# LedMatrix.net
KiCad netlist of a schematic drawn in Altium Designer
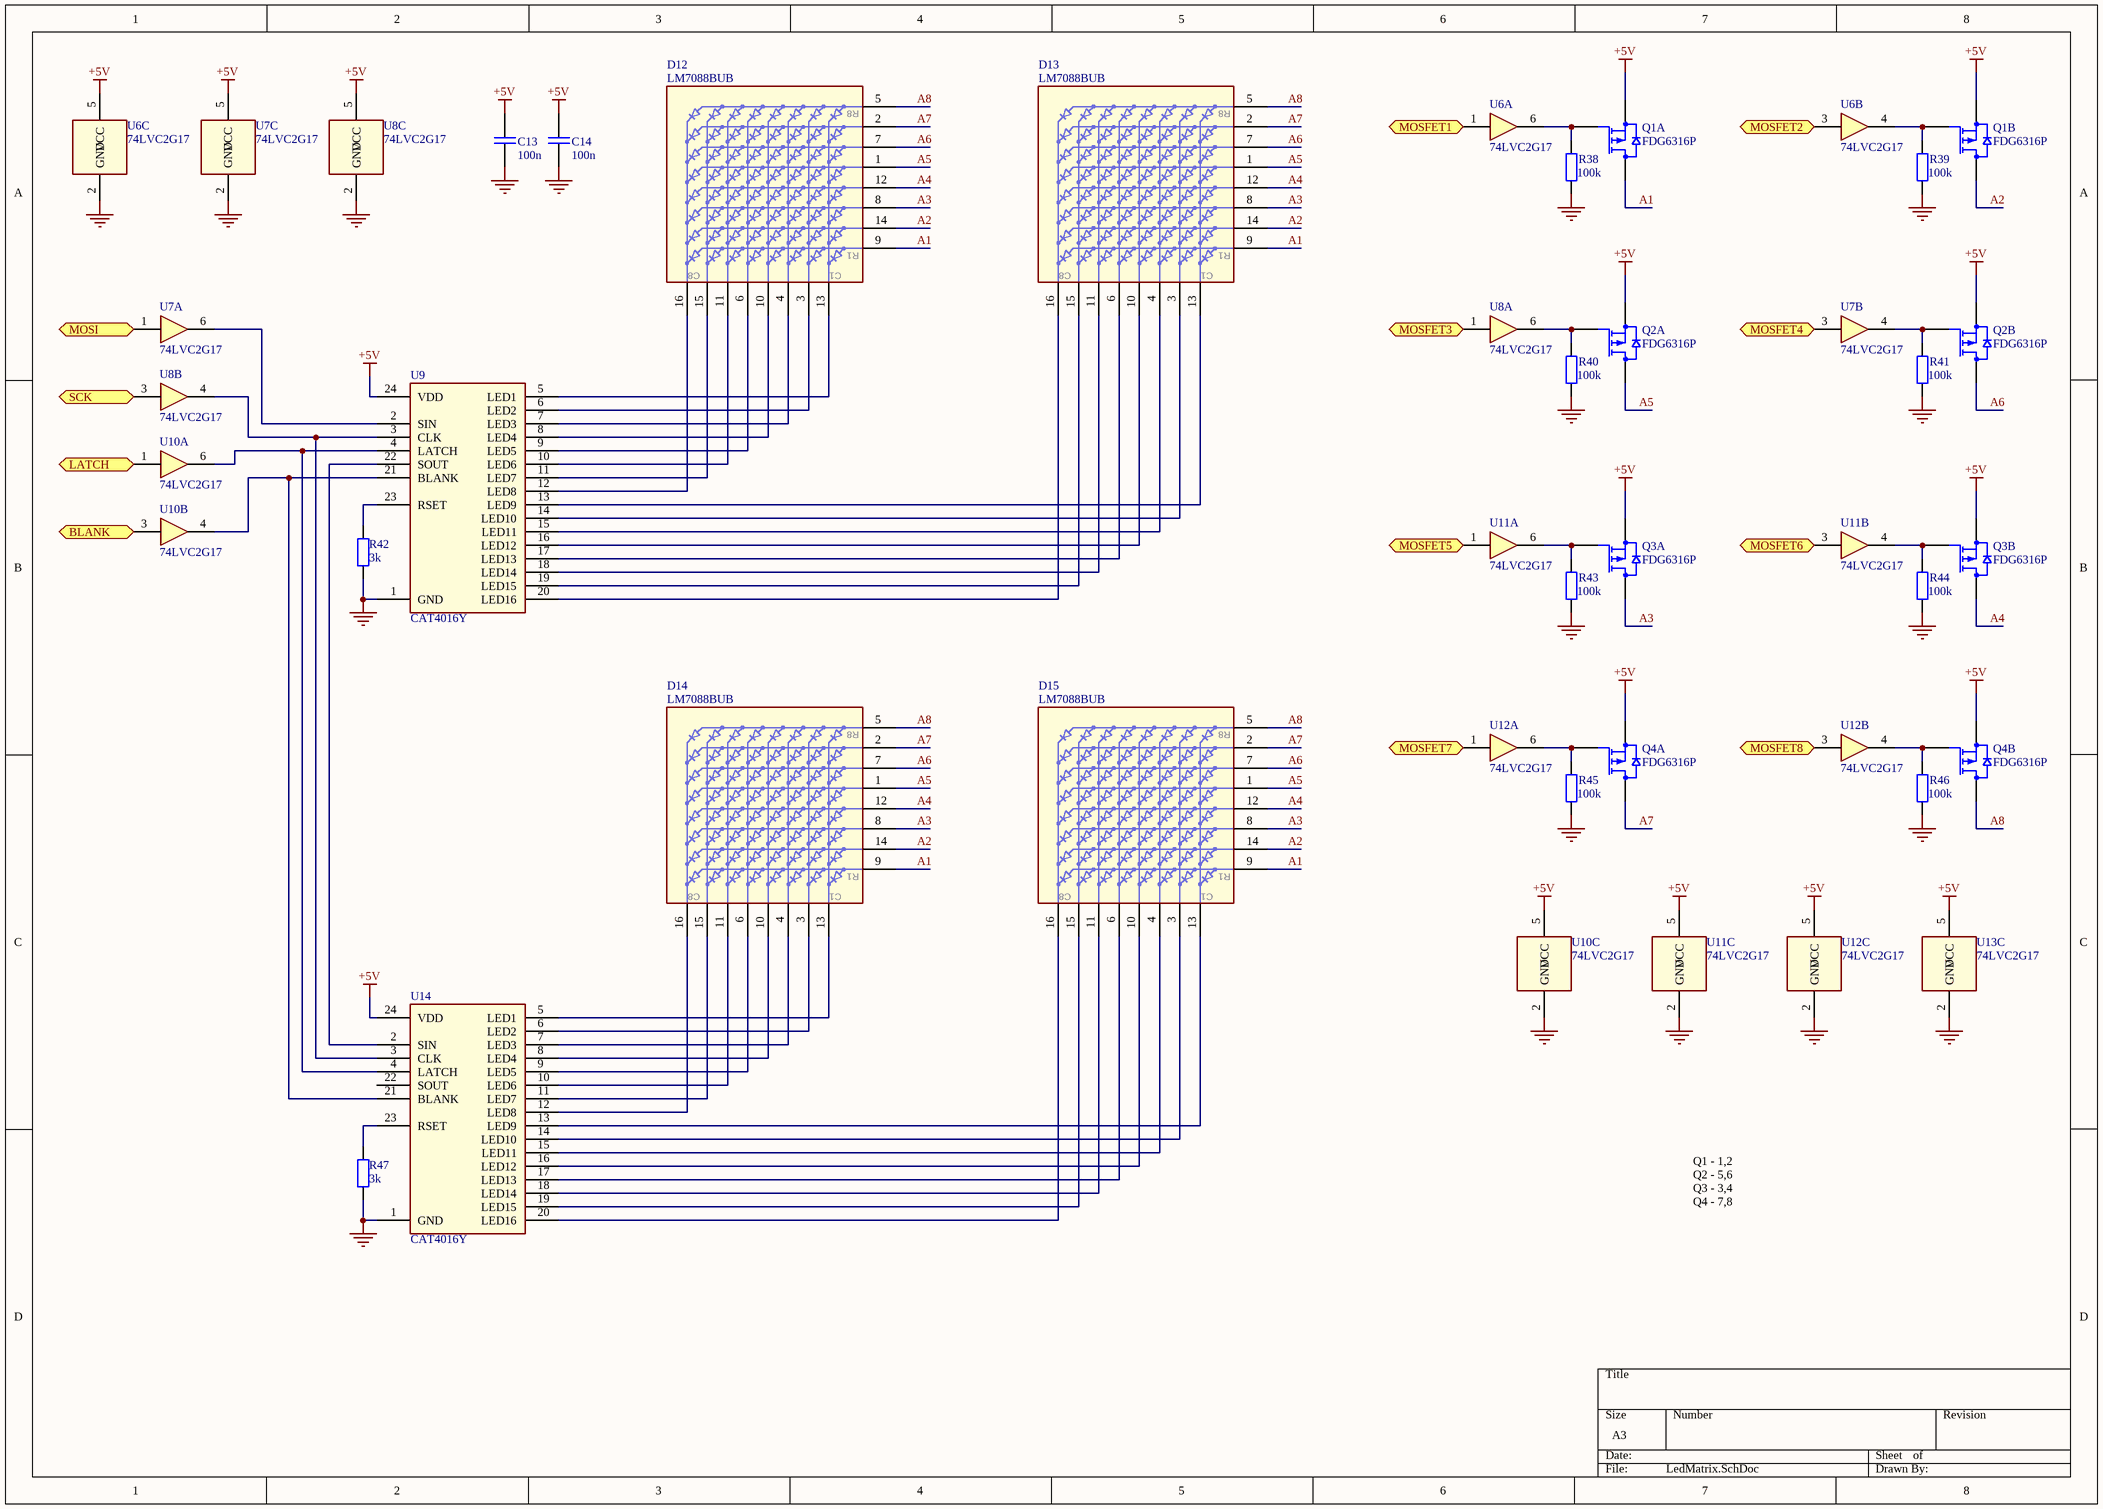
[diagram p0: LedMatrix.SchDoc]

(export (version "E")
  (design (tool "Eeschema 10.0.6"))
  (components
    (comp (ref "C13")
      (value "100n")
      (footprint "Cap 0603")
      (description "Capacitor")
      (libsource (lib "Komponente") (part "Cap"))
    )
    (comp (ref "C14")
      (value "100n")
      (footprint "Cap 0603")
      (description "Capacitor")
      (libsource (lib "Komponente") (part "Cap"))
    )
    (comp (ref "D12")
      (value "LM7088BUB")
      (footprint "KWM-19881 Series")
      (description "8x8 Dot Matrix LED Display (Common Row Anode), Blue")
      (libsource (lib "Komponente") (part "D LED LM7088BUB"))
    )
    (comp (ref "D13")
      (value "LM7088BUB")
      (footprint "KWM-19881 Series")
      (description "8x8 Dot Matrix LED Display (Common Row Anode), Blue")
      (libsource (lib "Komponente") (part "D LED LM7088BUB"))
    )
    (comp (ref "D14")
      (value "LM7088BUB")
      (footprint "KWM-19881 Series")
      (description "8x8 Dot Matrix LED Display (Common Row Anode), Blue")
      (libsource (lib "Komponente") (part "D LED LM7088BUB"))
    )
    (comp (ref "D15")
      (value "LM7088BUB")
      (footprint "KWM-19881 Series")
      (description "8x8 Dot Matrix LED Display (Common Row Anode), Blue")
      (libsource (lib "Komponente") (part "D LED LM7088BUB"))
    )
    (comp (ref "Q1")
      (value "FDG6316P")
      (footprint "SC-70-6 (SOT-363)")
      (description "P-Channel 1.8V Specified PowerTrench MOSFET")
      (libsource (lib "") (part "Q FDG6316P_1"))
    )
    (comp (ref "Q2")
      (value "FDG6316P")
      (footprint "SC-70-6 (SOT-363)")
      (description "P-Channel 1.8V Specified PowerTrench MOSFET")
      (libsource (lib "Komponente") (part "Q FDG6316P"))
    )
    (comp (ref "Q3")
      (value "FDG6316P")
      (footprint "SC-70-6 (SOT-363)")
      (description "P-Channel 1.8V Specified PowerTrench MOSFET")
      (libsource (lib "Komponente") (part "Q FDG6316P"))
    )
    (comp (ref "Q4")
      (value "FDG6316P")
      (footprint "SC-70-6 (SOT-363)")
      (description "P-Channel 1.8V Specified PowerTrench MOSFET")
      (libsource (lib "Komponente") (part "Q FDG6316P"))
    )
    (comp (ref "R38")
      (value "100k")
      (footprint "Res 0603")
      (description "Resistor")
      (libsource (lib "Komponente") (part "Res"))
    )
    (comp (ref "R39")
      (value "100k")
      (footprint "Res 0603")
      (description "Resistor")
      (libsource (lib "Komponente") (part "Res"))
    )
    (comp (ref "R40")
      (value "100k")
      (footprint "Res 0603")
      (description "Resistor")
      (libsource (lib "Komponente") (part "Res"))
    )
    (comp (ref "R41")
      (value "100k")
      (footprint "Res 0603")
      (description "Resistor")
      (libsource (lib "Komponente") (part "Res"))
    )
    (comp (ref "R42")
      (value "3k")
      (footprint "Res 0603")
      (description "Resistor")
      (libsource (lib "Komponente") (part "Res"))
    )
    (comp (ref "R43")
      (value "100k")
      (footprint "Res 0603")
      (description "Resistor")
      (libsource (lib "Komponente") (part "Res"))
    )
    (comp (ref "R44")
      (value "100k")
      (footprint "Res 0603")
      (description "Resistor")
      (libsource (lib "Komponente") (part "Res"))
    )
    (comp (ref "R45")
      (value "100k")
      (footprint "Res 0603")
      (description "Resistor")
      (libsource (lib "Komponente") (part "Res"))
    )
    (comp (ref "R46")
      (value "100k")
      (footprint "Res 0603")
      (description "Resistor")
      (libsource (lib "Komponente") (part "Res"))
    )
    (comp (ref "R47")
      (value "3k")
      (footprint "Res 0603")
      (description "Resistor")
      (libsource (lib "Komponente") (part "Res"))
    )
    (comp (ref "U6")
      (value "74LVC2G17")
      (footprint "SOT-23-6")
      (description "Dual non-inverting Schmitt trigger with 5 V tolerant input")
      (libsource (lib "Integrirane_komponente") (part "74LVC2G17"))
    )
    (comp (ref "U7")
      (value "74LVC2G17")
      (footprint "SOT-23-6")
      (description "Dual non-inverting Schmitt trigger with 5 V tolerant input")
      (libsource (lib "Integrirane_komponente") (part "74LVC2G17"))
    )
    (comp (ref "U8")
      (value "74LVC2G17")
      (footprint "SOT-23-6")
      (description "Dual non-inverting Schmitt trigger with 5 V tolerant input")
      (libsource (lib "Integrirane_komponente") (part "74LVC2G17"))
    )
    (comp (ref "U9")
      (value "CAT4016Y")
      (footprint "TSSOP-24")
      (description "16-Channel Constant Current LED Driver")
      (libsource (lib "Integrirane_komponente") (part "CAT4016Y"))
    )
    (comp (ref "U10")
      (value "74LVC2G17")
      (footprint "SOT-23-6")
      (description "Dual non-inverting Schmitt trigger with 5 V tolerant input")
      (libsource (lib "Integrirane_komponente") (part "74LVC2G17"))
    )
    (comp (ref "U11")
      (value "74LVC2G17")
      (footprint "SOT-23-6")
      (description "Dual non-inverting Schmitt trigger with 5 V tolerant input")
      (libsource (lib "Integrirane_komponente") (part "74LVC2G17"))
    )
    (comp (ref "U12")
      (value "74LVC2G17")
      (footprint "SOT-23-6")
      (description "Dual non-inverting Schmitt trigger with 5 V tolerant input")
      (libsource (lib "Integrirane_komponente") (part "74LVC2G17"))
    )
    (comp (ref "U13")
      (value "74LVC2G17")
      (footprint "SOT-23-6")
      (description "Dual non-inverting Schmitt trigger with 5 V tolerant input")
      (libsource (lib "Integrirane_komponente") (part "74LVC2G17"))
    )
    (comp (ref "U14")
      (value "CAT4016Y")
      (footprint "TSSOP-24")
      (description "16-Channel Constant Current LED Driver")
      (libsource (lib "Integrirane_komponente") (part "CAT4016Y"))
    )
  )
  (nets
    (net (code "1") (name "+5V") (class "Default")
      (node (ref "C13") (pin "1") (pinfunction "1_1") (pintype "passive"))
      (node (ref "C14") (pin "1") (pinfunction "1_1") (pintype "passive"))
      (node (ref "Q1") (pin "1") (pinfunction "S1_1") (pintype "passive"))
      (node (ref "Q1") (pin "4") (pinfunction "S2_4") (pintype "passive"))
      (node (ref "Q2") (pin "1") (pinfunction "S1_1") (pintype "passive"))
      (node (ref "Q2") (pin "4") (pinfunction "S2_4") (pintype "passive"))
      (node (ref "Q3") (pin "1") (pinfunction "S1_1") (pintype "passive"))
      (node (ref "Q3") (pin "4") (pinfunction "S2_4") (pintype "passive"))
      (node (ref "Q4") (pin "1") (pinfunction "S1_1") (pintype "passive"))
      (node (ref "Q4") (pin "4") (pinfunction "S2_4") (pintype "passive"))
      (node (ref "U10") (pin "5") (pinfunction "VCC_5") (pintype "passive"))
      (node (ref "U11") (pin "5") (pinfunction "VCC_5") (pintype "passive"))
      (node (ref "U12") (pin "5") (pinfunction "VCC_5") (pintype "passive"))
      (node (ref "U13") (pin "5") (pinfunction "VCC_5") (pintype "passive"))
      (node (ref "U14") (pin "24") (pinfunction "VDD_24") (pintype "passive"))
      (node (ref "U6") (pin "5") (pinfunction "VCC_5") (pintype "passive"))
      (node (ref "U7") (pin "5") (pinfunction "VCC_5") (pintype "passive"))
      (node (ref "U8") (pin "5") (pinfunction "VCC_5") (pintype "passive"))
      (node (ref "U9") (pin "24") (pinfunction "VDD_24") (pintype "passive"))
    )
    (net (code "2") (name "/A1") (class "Default")
      (node (ref "D12") (pin "9") (pinfunction "R1_9") (pintype "passive"))
      (node (ref "D13") (pin "9") (pinfunction "R1_9") (pintype "passive"))
      (node (ref "D14") (pin "9") (pinfunction "R1_9") (pintype "passive"))
      (node (ref "D15") (pin "9") (pinfunction "R1_9") (pintype "passive"))
      (node (ref "Q1") (pin "6") (pinfunction "D1_6") (pintype "passive"))
    )
    (net (code "3") (name "/A2") (class "Default")
      (node (ref "D12") (pin "14") (pinfunction "R2_14") (pintype "passive"))
      (node (ref "D13") (pin "14") (pinfunction "R2_14") (pintype "passive"))
      (node (ref "D14") (pin "14") (pinfunction "R2_14") (pintype "passive"))
      (node (ref "D15") (pin "14") (pinfunction "R2_14") (pintype "passive"))
      (node (ref "Q1") (pin "3") (pinfunction "D2_3") (pintype "passive"))
    )
    (net (code "4") (name "/A3") (class "Default")
      (node (ref "D12") (pin "8") (pinfunction "R3_8") (pintype "passive"))
      (node (ref "D13") (pin "8") (pinfunction "R3_8") (pintype "passive"))
      (node (ref "D14") (pin "8") (pinfunction "R3_8") (pintype "passive"))
      (node (ref "D15") (pin "8") (pinfunction "R3_8") (pintype "passive"))
      (node (ref "Q3") (pin "6") (pinfunction "D1_6") (pintype "passive"))
    )
    (net (code "5") (name "/A4") (class "Default")
      (node (ref "D12") (pin "12") (pinfunction "R4_12") (pintype "passive"))
      (node (ref "D13") (pin "12") (pinfunction "R4_12") (pintype "passive"))
      (node (ref "D14") (pin "12") (pinfunction "R4_12") (pintype "passive"))
      (node (ref "D15") (pin "12") (pinfunction "R4_12") (pintype "passive"))
      (node (ref "Q3") (pin "3") (pinfunction "D2_3") (pintype "passive"))
    )
    (net (code "6") (name "/A5") (class "Default")
      (node (ref "D12") (pin "1") (pinfunction "R5_1") (pintype "passive"))
      (node (ref "D13") (pin "1") (pinfunction "R5_1") (pintype "passive"))
      (node (ref "D14") (pin "1") (pinfunction "R5_1") (pintype "passive"))
      (node (ref "D15") (pin "1") (pinfunction "R5_1") (pintype "passive"))
      (node (ref "Q2") (pin "6") (pinfunction "D1_6") (pintype "passive"))
    )
    (net (code "7") (name "/A6") (class "Default")
      (node (ref "D12") (pin "7") (pinfunction "R6_7") (pintype "passive"))
      (node (ref "D13") (pin "7") (pinfunction "R6_7") (pintype "passive"))
      (node (ref "D14") (pin "7") (pinfunction "R6_7") (pintype "passive"))
      (node (ref "D15") (pin "7") (pinfunction "R6_7") (pintype "passive"))
      (node (ref "Q2") (pin "3") (pinfunction "D2_3") (pintype "passive"))
    )
    (net (code "8") (name "/A7") (class "Default")
      (node (ref "D12") (pin "2") (pinfunction "R7_2") (pintype "passive"))
      (node (ref "D13") (pin "2") (pinfunction "R7_2") (pintype "passive"))
      (node (ref "D14") (pin "2") (pinfunction "R7_2") (pintype "passive"))
      (node (ref "D15") (pin "2") (pinfunction "R7_2") (pintype "passive"))
      (node (ref "Q4") (pin "6") (pinfunction "D1_6") (pintype "passive"))
    )
    (net (code "9") (name "/A8") (class "Default")
      (node (ref "D12") (pin "5") (pinfunction "R8_5") (pintype "passive"))
      (node (ref "D13") (pin "5") (pinfunction "R8_5") (pintype "passive"))
      (node (ref "D14") (pin "5") (pinfunction "R8_5") (pintype "passive"))
      (node (ref "D15") (pin "5") (pinfunction "R8_5") (pintype "passive"))
      (node (ref "Q4") (pin "3") (pinfunction "D2_3") (pintype "passive"))
    )
    (net (code "10") (name "/BLANK") (class "Default")
      (node (ref "U10") (pin "3") (pinfunction "3_3") (pintype "passive"))
    )
    (net (code "11") (name "/LATCH") (class "Default")
      (node (ref "U10") (pin "1") (pinfunction "1_1") (pintype "passive"))
    )
    (net (code "12") (name "/MOSFET1") (class "Default")
      (node (ref "U6") (pin "1") (pinfunction "1_1") (pintype "passive"))
    )
    (net (code "13") (name "/MOSFET2") (class "Default")
      (node (ref "U6") (pin "3") (pinfunction "3_3") (pintype "passive"))
    )
    (net (code "14") (name "/MOSFET3") (class "Default")
      (node (ref "U8") (pin "1") (pinfunction "1_1") (pintype "passive"))
    )
    (net (code "15") (name "/MOSFET4") (class "Default")
      (node (ref "U7") (pin "3") (pinfunction "3_3") (pintype "passive"))
    )
    (net (code "16") (name "/MOSFET5") (class "Default")
      (node (ref "U11") (pin "1") (pinfunction "1_1") (pintype "passive"))
    )
    (net (code "17") (name "/MOSFET6") (class "Default")
      (node (ref "U11") (pin "3") (pinfunction "3_3") (pintype "passive"))
    )
    (net (code "18") (name "/MOSFET7") (class "Default")
      (node (ref "U12") (pin "1") (pinfunction "1_1") (pintype "passive"))
    )
    (net (code "19") (name "/MOSFET8") (class "Default")
      (node (ref "U12") (pin "3") (pinfunction "3_3") (pintype "passive"))
    )
    (net (code "20") (name "/MOSI") (class "Default")
      (node (ref "U7") (pin "1") (pinfunction "1_1") (pintype "passive"))
    )
    (net (code "21") (name "/SCK") (class "Default")
      (node (ref "U8") (pin "3") (pinfunction "3_3") (pintype "passive"))
    )
    (net (code "22") (name "GND") (class "Default")
      (node (ref "C13") (pin "2") (pinfunction "2_2") (pintype "passive"))
      (node (ref "C14") (pin "2") (pinfunction "2_2") (pintype "passive"))
      (node (ref "R38") (pin "1") (pinfunction "1_1") (pintype "passive"))
      (node (ref "R39") (pin "1") (pinfunction "1_1") (pintype "passive"))
      (node (ref "R40") (pin "1") (pinfunction "1_1") (pintype "passive"))
      (node (ref "R41") (pin "1") (pinfunction "1_1") (pintype "passive"))
      (node (ref "R42") (pin "1") (pinfunction "1_1") (pintype "passive"))
      (node (ref "R43") (pin "1") (pinfunction "1_1") (pintype "passive"))
      (node (ref "R44") (pin "1") (pinfunction "1_1") (pintype "passive"))
      (node (ref "R45") (pin "1") (pinfunction "1_1") (pintype "passive"))
      (node (ref "R46") (pin "1") (pinfunction "1_1") (pintype "passive"))
      (node (ref "R47") (pin "1") (pinfunction "1_1") (pintype "passive"))
      (node (ref "U10") (pin "2") (pinfunction "GND_2") (pintype "passive"))
      (node (ref "U11") (pin "2") (pinfunction "GND_2") (pintype "passive"))
      (node (ref "U12") (pin "2") (pinfunction "GND_2") (pintype "passive"))
      (node (ref "U13") (pin "2") (pinfunction "GND_2") (pintype "passive"))
      (node (ref "U14") (pin "1") (pinfunction "GND_1") (pintype "passive"))
      (node (ref "U6") (pin "2") (pinfunction "GND_2") (pintype "passive"))
      (node (ref "U7") (pin "2") (pinfunction "GND_2") (pintype "passive"))
      (node (ref "U8") (pin "2") (pinfunction "GND_2") (pintype "passive"))
      (node (ref "U9") (pin "1") (pinfunction "GND_1") (pintype "passive"))
    )
    (net (code "23") (name "Net-(D12-C1)") (class "Default")
      (node (ref "D12") (pin "13") (pinfunction "C1_13") (pintype "passive"))
      (node (ref "U9") (pin "5") (pinfunction "LED1_5") (pintype "passive"))
    )
    (net (code "24") (name "Net-(D12-C2)") (class "Default")
      (node (ref "D12") (pin "3") (pinfunction "C2_3") (pintype "passive"))
      (node (ref "U9") (pin "6") (pinfunction "LED2_6") (pintype "passive"))
    )
    (net (code "25") (name "Net-(D12-C3)") (class "Default")
      (node (ref "D12") (pin "4") (pinfunction "C3_4") (pintype "passive"))
      (node (ref "U9") (pin "7") (pinfunction "LED3_7") (pintype "passive"))
    )
    (net (code "26") (name "Net-(D12-C4)") (class "Default")
      (node (ref "D12") (pin "10") (pinfunction "C4_10") (pintype "passive"))
      (node (ref "U9") (pin "8") (pinfunction "LED4_8") (pintype "passive"))
    )
    (net (code "27") (name "Net-(D12-C5)") (class "Default")
      (node (ref "D12") (pin "6") (pinfunction "C5_6") (pintype "passive"))
      (node (ref "U9") (pin "9") (pinfunction "LED5_9") (pintype "passive"))
    )
    (net (code "28") (name "Net-(D12-C6)") (class "Default")
      (node (ref "D12") (pin "11") (pinfunction "C6_11") (pintype "passive"))
      (node (ref "U9") (pin "10") (pinfunction "LED6_10") (pintype "passive"))
    )
    (net (code "29") (name "Net-(D12-C7)") (class "Default")
      (node (ref "D12") (pin "15") (pinfunction "C7_15") (pintype "passive"))
      (node (ref "U9") (pin "11") (pinfunction "LED7_11") (pintype "passive"))
    )
    (net (code "30") (name "Net-(D12-C8)") (class "Default")
      (node (ref "D12") (pin "16") (pinfunction "C8_16") (pintype "passive"))
      (node (ref "U9") (pin "12") (pinfunction "LED8_12") (pintype "passive"))
    )
    (net (code "31") (name "Net-(D13-C1)") (class "Default")
      (node (ref "D13") (pin "13") (pinfunction "C1_13") (pintype "passive"))
      (node (ref "U9") (pin "13") (pinfunction "LED9_13") (pintype "passive"))
    )
    (net (code "32") (name "Net-(D13-C2)") (class "Default")
      (node (ref "D13") (pin "3") (pinfunction "C2_3") (pintype "passive"))
      (node (ref "U9") (pin "14") (pinfunction "LED10_14") (pintype "passive"))
    )
    (net (code "33") (name "Net-(D13-C3)") (class "Default")
      (node (ref "D13") (pin "4") (pinfunction "C3_4") (pintype "passive"))
      (node (ref "U9") (pin "15") (pinfunction "LED11_15") (pintype "passive"))
    )
    (net (code "34") (name "Net-(D13-C4)") (class "Default")
      (node (ref "D13") (pin "10") (pinfunction "C4_10") (pintype "passive"))
      (node (ref "U9") (pin "16") (pinfunction "LED12_16") (pintype "passive"))
    )
    (net (code "35") (name "Net-(D13-C5)") (class "Default")
      (node (ref "D13") (pin "6") (pinfunction "C5_6") (pintype "passive"))
      (node (ref "U9") (pin "17") (pinfunction "LED13_17") (pintype "passive"))
    )
    (net (code "36") (name "Net-(D13-C6)") (class "Default")
      (node (ref "D13") (pin "11") (pinfunction "C6_11") (pintype "passive"))
      (node (ref "U9") (pin "18") (pinfunction "LED14_18") (pintype "passive"))
    )
    (net (code "37") (name "Net-(D13-C7)") (class "Default")
      (node (ref "D13") (pin "15") (pinfunction "C7_15") (pintype "passive"))
      (node (ref "U9") (pin "19") (pinfunction "LED15_19") (pintype "passive"))
    )
    (net (code "38") (name "Net-(D13-C8)") (class "Default")
      (node (ref "D13") (pin "16") (pinfunction "C8_16") (pintype "passive"))
      (node (ref "U9") (pin "20") (pinfunction "LED16_20") (pintype "passive"))
    )
    (net (code "39") (name "Net-(D14-C1)") (class "Default")
      (node (ref "D14") (pin "13") (pinfunction "C1_13") (pintype "passive"))
      (node (ref "U14") (pin "5") (pinfunction "LED1_5") (pintype "passive"))
    )
    (net (code "40") (name "Net-(D14-C2)") (class "Default")
      (node (ref "D14") (pin "3") (pinfunction "C2_3") (pintype "passive"))
      (node (ref "U14") (pin "6") (pinfunction "LED2_6") (pintype "passive"))
    )
    (net (code "41") (name "Net-(D14-C3)") (class "Default")
      (node (ref "D14") (pin "4") (pinfunction "C3_4") (pintype "passive"))
      (node (ref "U14") (pin "7") (pinfunction "LED3_7") (pintype "passive"))
    )
    (net (code "42") (name "Net-(D14-C4)") (class "Default")
      (node (ref "D14") (pin "10") (pinfunction "C4_10") (pintype "passive"))
      (node (ref "U14") (pin "8") (pinfunction "LED4_8") (pintype "passive"))
    )
    (net (code "43") (name "Net-(D14-C5)") (class "Default")
      (node (ref "D14") (pin "6") (pinfunction "C5_6") (pintype "passive"))
      (node (ref "U14") (pin "9") (pinfunction "LED5_9") (pintype "passive"))
    )
    (net (code "44") (name "Net-(D14-C6)") (class "Default")
      (node (ref "D14") (pin "11") (pinfunction "C6_11") (pintype "passive"))
      (node (ref "U14") (pin "10") (pinfunction "LED6_10") (pintype "passive"))
    )
    (net (code "45") (name "Net-(D14-C7)") (class "Default")
      (node (ref "D14") (pin "15") (pinfunction "C7_15") (pintype "passive"))
      (node (ref "U14") (pin "11") (pinfunction "LED7_11") (pintype "passive"))
    )
    (net (code "46") (name "Net-(D14-C8)") (class "Default")
      (node (ref "D14") (pin "16") (pinfunction "C8_16") (pintype "passive"))
      (node (ref "U14") (pin "12") (pinfunction "LED8_12") (pintype "passive"))
    )
    (net (code "47") (name "Net-(D15-C1)") (class "Default")
      (node (ref "D15") (pin "13") (pinfunction "C1_13") (pintype "passive"))
      (node (ref "U14") (pin "13") (pinfunction "LED9_13") (pintype "passive"))
    )
    (net (code "48") (name "Net-(D15-C2)") (class "Default")
      (node (ref "D15") (pin "3") (pinfunction "C2_3") (pintype "passive"))
      (node (ref "U14") (pin "14") (pinfunction "LED10_14") (pintype "passive"))
    )
    (net (code "49") (name "Net-(D15-C3)") (class "Default")
      (node (ref "D15") (pin "4") (pinfunction "C3_4") (pintype "passive"))
      (node (ref "U14") (pin "15") (pinfunction "LED11_15") (pintype "passive"))
    )
    (net (code "50") (name "Net-(D15-C4)") (class "Default")
      (node (ref "D15") (pin "10") (pinfunction "C4_10") (pintype "passive"))
      (node (ref "U14") (pin "16") (pinfunction "LED12_16") (pintype "passive"))
    )
    (net (code "51") (name "Net-(D15-C5)") (class "Default")
      (node (ref "D15") (pin "6") (pinfunction "C5_6") (pintype "passive"))
      (node (ref "U14") (pin "17") (pinfunction "LED13_17") (pintype "passive"))
    )
    (net (code "52") (name "Net-(D15-C6)") (class "Default")
      (node (ref "D15") (pin "11") (pinfunction "C6_11") (pintype "passive"))
      (node (ref "U14") (pin "18") (pinfunction "LED14_18") (pintype "passive"))
    )
    (net (code "53") (name "Net-(D15-C7)") (class "Default")
      (node (ref "D15") (pin "15") (pinfunction "C7_15") (pintype "passive"))
      (node (ref "U14") (pin "19") (pinfunction "LED15_19") (pintype "passive"))
    )
    (net (code "54") (name "Net-(D15-C8)") (class "Default")
      (node (ref "D15") (pin "16") (pinfunction "C8_16") (pintype "passive"))
      (node (ref "U14") (pin "20") (pinfunction "LED16_20") (pintype "passive"))
    )
    (net (code "55") (name "Net-(Q1A-G1)") (class "Default")
      (node (ref "Q1") (pin "2") (pinfunction "G1_2") (pintype "passive"))
      (node (ref "R38") (pin "2") (pinfunction "2_2") (pintype "passive"))
      (node (ref "U6") (pin "6") (pinfunction "6_6") (pintype "passive"))
    )
    (net (code "56") (name "Net-(Q1B-G2)") (class "Default")
      (node (ref "Q1") (pin "5") (pinfunction "G2_5") (pintype "passive"))
      (node (ref "R39") (pin "2") (pinfunction "2_2") (pintype "passive"))
      (node (ref "U6") (pin "4") (pinfunction "4_4") (pintype "passive"))
    )
    (net (code "57") (name "Net-(Q2A-G1)") (class "Default")
      (node (ref "Q2") (pin "2") (pinfunction "G1_2") (pintype "passive"))
      (node (ref "R40") (pin "2") (pinfunction "2_2") (pintype "passive"))
      (node (ref "U8") (pin "6") (pinfunction "6_6") (pintype "passive"))
    )
    (net (code "58") (name "Net-(Q2B-G2)") (class "Default")
      (node (ref "Q2") (pin "5") (pinfunction "G2_5") (pintype "passive"))
      (node (ref "R41") (pin "2") (pinfunction "2_2") (pintype "passive"))
      (node (ref "U7") (pin "4") (pinfunction "4_4") (pintype "passive"))
    )
    (net (code "59") (name "Net-(Q3A-G1)") (class "Default")
      (node (ref "Q3") (pin "2") (pinfunction "G1_2") (pintype "passive"))
      (node (ref "R43") (pin "2") (pinfunction "2_2") (pintype "passive"))
      (node (ref "U11") (pin "6") (pinfunction "6_6") (pintype "passive"))
    )
    (net (code "60") (name "Net-(Q3B-G2)") (class "Default")
      (node (ref "Q3") (pin "5") (pinfunction "G2_5") (pintype "passive"))
      (node (ref "R44") (pin "2") (pinfunction "2_2") (pintype "passive"))
      (node (ref "U11") (pin "4") (pinfunction "4_4") (pintype "passive"))
    )
    (net (code "61") (name "Net-(Q4A-G1)") (class "Default")
      (node (ref "Q4") (pin "2") (pinfunction "G1_2") (pintype "passive"))
      (node (ref "R45") (pin "2") (pinfunction "2_2") (pintype "passive"))
      (node (ref "U12") (pin "6") (pinfunction "6_6") (pintype "passive"))
    )
    (net (code "62") (name "Net-(Q4B-G2)") (class "Default")
      (node (ref "Q4") (pin "5") (pinfunction "G2_5") (pintype "passive"))
      (node (ref "R46") (pin "2") (pinfunction "2_2") (pintype "passive"))
      (node (ref "U12") (pin "4") (pinfunction "4_4") (pintype "passive"))
    )
    (net (code "63") (name "Net-(U9-RSET)") (class "Default")
      (node (ref "R42") (pin "2") (pinfunction "2_2") (pintype "passive"))
      (node (ref "U9") (pin "23") (pinfunction "RSET_23") (pintype "passive"))
    )
    (net (code "64") (name "Net-(U9-SIN)") (class "Default")
      (node (ref "U7") (pin "6") (pinfunction "6_6") (pintype "passive"))
      (node (ref "U9") (pin "2") (pinfunction "SIN_2") (pintype "passive"))
    )
    (net (code "65") (name "Net-(U14-BLANK)") (class "Default")
      (node (ref "U10") (pin "4") (pinfunction "4_4") (pintype "passive"))
      (node (ref "U14") (pin "21") (pinfunction "BLANK_21") (pintype "passive"))
      (node (ref "U9") (pin "21") (pinfunction "BLANK_21") (pintype "passive"))
    )
    (net (code "66") (name "Net-(U14-CLK)") (class "Default")
      (node (ref "U14") (pin "3") (pinfunction "CLK_3") (pintype "passive"))
      (node (ref "U8") (pin "4") (pinfunction "4_4") (pintype "passive"))
      (node (ref "U9") (pin "3") (pinfunction "CLK_3") (pintype "passive"))
    )
    (net (code "67") (name "Net-(U14-LATCH)") (class "Default")
      (node (ref "U10") (pin "6") (pinfunction "6_6") (pintype "passive"))
      (node (ref "U14") (pin "4") (pinfunction "LATCH_4") (pintype "passive"))
      (node (ref "U9") (pin "4") (pinfunction "LATCH_4") (pintype "passive"))
    )
    (net (code "68") (name "Net-(U14-RSET)") (class "Default")
      (node (ref "R47") (pin "2") (pinfunction "2_2") (pintype "passive"))
      (node (ref "U14") (pin "23") (pinfunction "RSET_23") (pintype "passive"))
    )
    (net (code "69") (name "Net-(U14-SIN)") (class "Default")
      (node (ref "U14") (pin "2") (pinfunction "SIN_2") (pintype "passive"))
      (node (ref "U9") (pin "22") (pinfunction "SOUT_22") (pintype "passive"))
    )
    (net (code "70") (name "unconnected-(U14-SOUT-Pad22)") (class "Default")
      (node (ref "U14") (pin "22") (pinfunction "SOUT_22") (pintype "passive"))
    )
  )
)
